# Precision_Arduino_Charlieplex_2_0.net
KiCad netlist of a schematic drawn in EAGLE
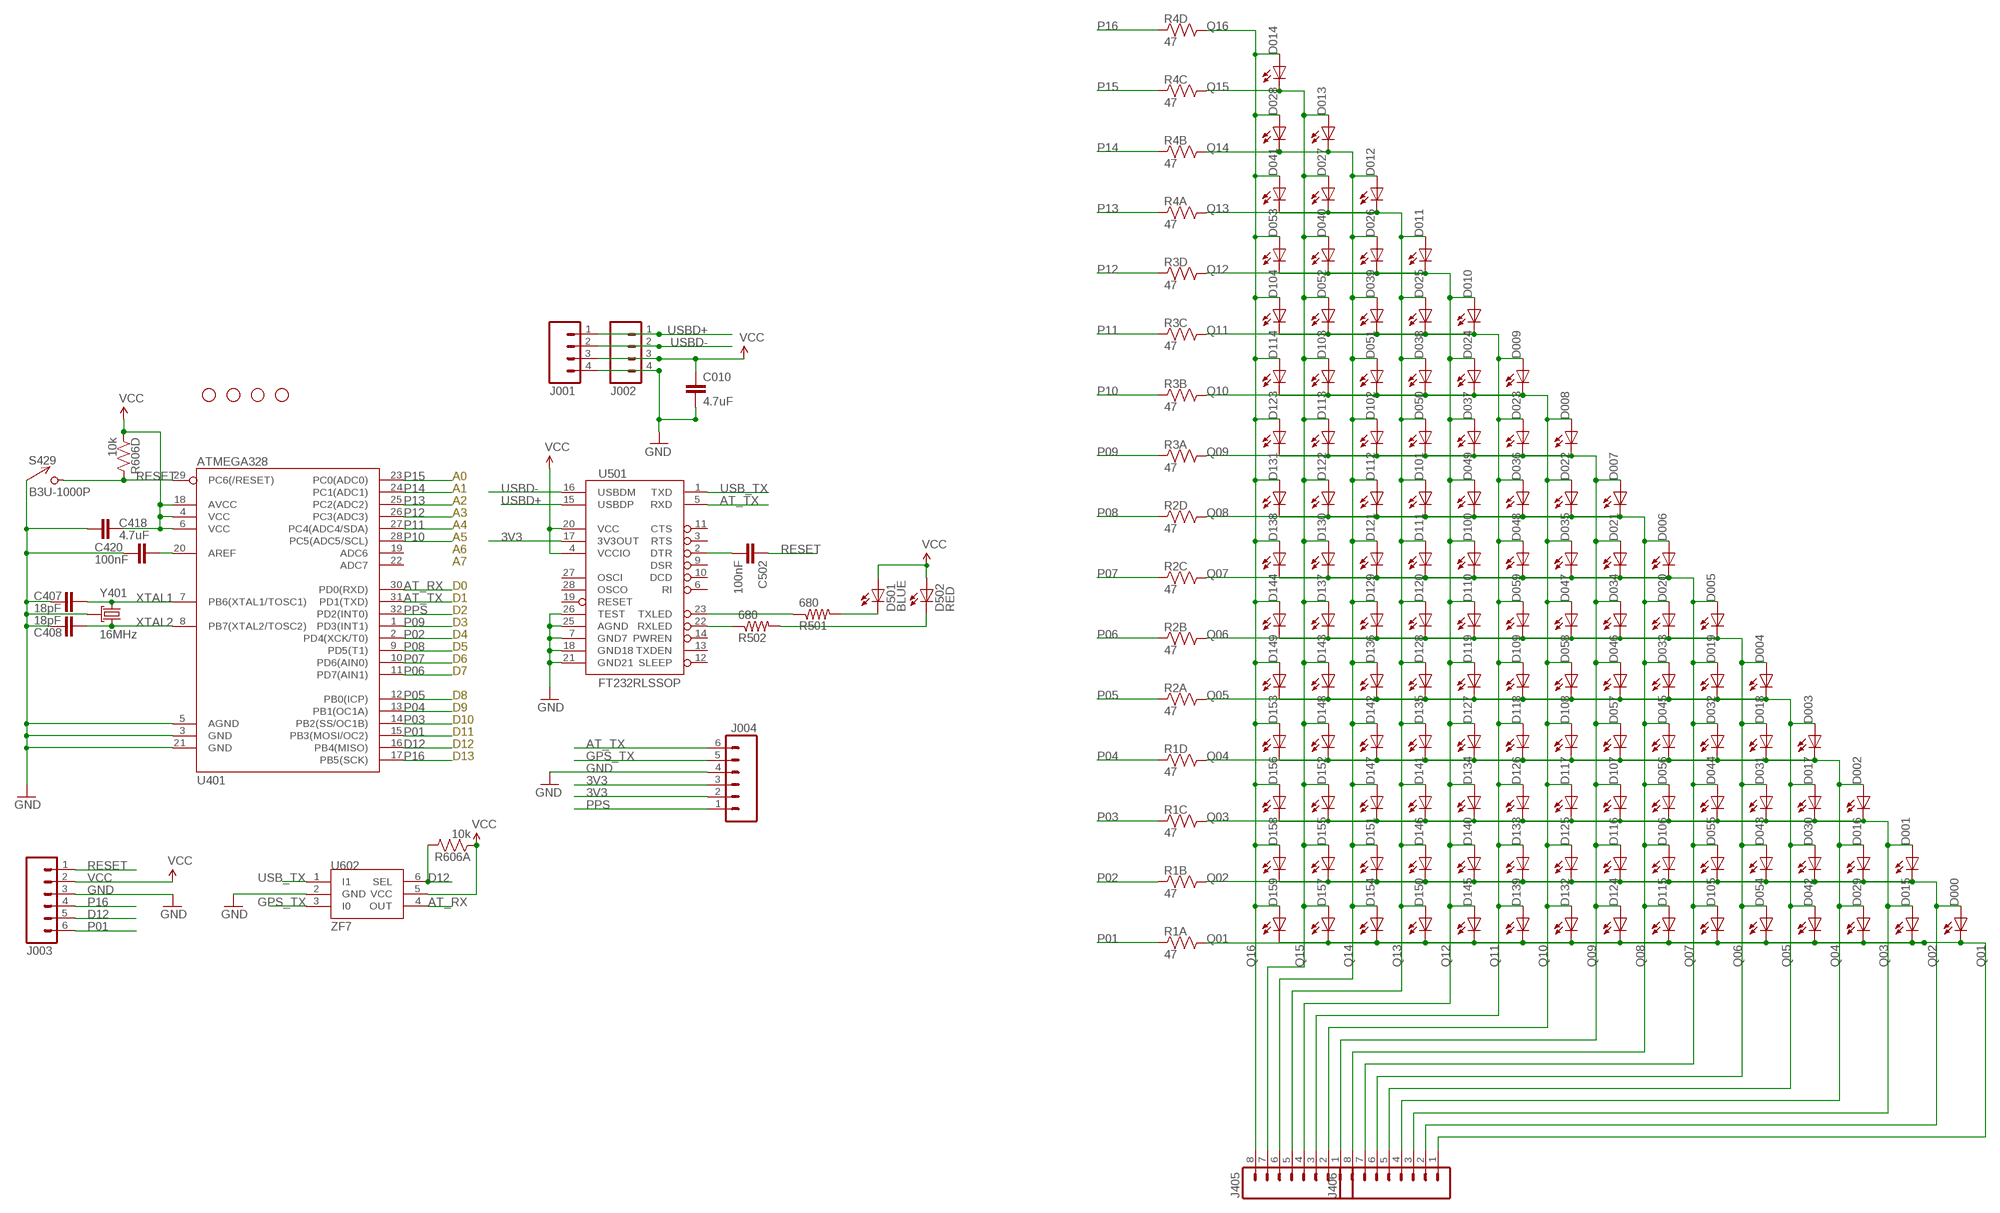
[diagram p0: schematic, sheet 1]

(export (version "E")
  (design (tool "Eeschema 10.0.6"))
  (components
    (comp (ref "C010")
      (value "4.7uF")
      (footprint "eagle-import:0603-CAP")
      (libsource (lib "eagle-import") (part "CAP0603-CAP"))
    )
    (comp (ref "C407")
      (value "18pF")
      (footprint "eagle-import:0603-CAP")
      (libsource (lib "eagle-import") (part "CAP0603-CAP"))
    )
    (comp (ref "C408")
      (value "18pF")
      (footprint "eagle-import:0603-CAP")
      (libsource (lib "eagle-import") (part "CAP0603-CAP"))
    )
    (comp (ref "C418")
      (value "4.7uF")
      (footprint "eagle-import:0603-CAP")
      (libsource (lib "eagle-import") (part "CAP0603-CAP"))
    )
    (comp (ref "C420")
      (value "100nF")
      (footprint "eagle-import:0603-CAP")
      (libsource (lib "eagle-import") (part "CAP0603-CAP"))
    )
    (comp (ref "C502")
      (value "100nF")
      (footprint "eagle-import:0603-CAP")
      (libsource (lib "eagle-import") (part "CAP0603-CAP"))
    )
    (comp (ref "D000")
      (value "HOUR")
      (footprint "eagle-import:LED-0603")
      (libsource (lib "eagle-import") (part "LED0603"))
    )
    (comp (ref "D001")
      (value "HOUR")
      (footprint "eagle-import:LED-0603")
      (libsource (lib "eagle-import") (part "LED0603"))
    )
    (comp (ref "D002")
      (value "HOUR")
      (footprint "eagle-import:LED-0603")
      (libsource (lib "eagle-import") (part "LED0603"))
    )
    (comp (ref "D003")
      (value "HOUR")
      (footprint "eagle-import:LED-0603")
      (libsource (lib "eagle-import") (part "LED0603"))
    )
    (comp (ref "D004")
      (value "HOUR")
      (footprint "eagle-import:LED-0603")
      (libsource (lib "eagle-import") (part "LED0603"))
    )
    (comp (ref "D005")
      (value "HOUR")
      (footprint "eagle-import:LED-0603")
      (libsource (lib "eagle-import") (part "LED0603"))
    )
    (comp (ref "D006")
      (value "HOUR")
      (footprint "eagle-import:LED-0603")
      (libsource (lib "eagle-import") (part "LED0603"))
    )
    (comp (ref "D007")
      (value "HOUR")
      (footprint "eagle-import:LED-0603")
      (libsource (lib "eagle-import") (part "LED0603"))
    )
    (comp (ref "D008")
      (value "HOUR")
      (footprint "eagle-import:LED-0603")
      (libsource (lib "eagle-import") (part "LED0603"))
    )
    (comp (ref "D009")
      (value "HOUR")
      (footprint "eagle-import:LED-0603")
      (libsource (lib "eagle-import") (part "LED0603"))
    )
    (comp (ref "D010")
      (value "HOUR")
      (footprint "eagle-import:LED-0603")
      (libsource (lib "eagle-import") (part "LED0603"))
    )
    (comp (ref "D011")
      (value "HOUR")
      (footprint "eagle-import:LED-0603")
      (libsource (lib "eagle-import") (part "LED0603"))
    )
    (comp (ref "D012")
      (value "HOUR")
      (footprint "eagle-import:LED-0603")
      (libsource (lib "eagle-import") (part "LED0603"))
    )
    (comp (ref "D013")
      (value "HOUR")
      (footprint "eagle-import:LED-0603")
      (libsource (lib "eagle-import") (part "LED0603"))
    )
    (comp (ref "D014")
      (value "HOUR")
      (footprint "eagle-import:LED-0603")
      (libsource (lib "eagle-import") (part "LED0603"))
    )
    (comp (ref "D015")
      (value "HOUR")
      (footprint "eagle-import:LED-0603")
      (libsource (lib "eagle-import") (part "LED0603"))
    )
    (comp (ref "D016")
      (value "HOUR")
      (footprint "eagle-import:LED-0603")
      (libsource (lib "eagle-import") (part "LED0603"))
    )
    (comp (ref "D017")
      (value "HOUR")
      (footprint "eagle-import:LED-0603")
      (libsource (lib "eagle-import") (part "LED0603"))
    )
    (comp (ref "D018")
      (value "HOUR")
      (footprint "eagle-import:LED-0603")
      (libsource (lib "eagle-import") (part "LED0603"))
    )
    (comp (ref "D019")
      (value "HOUR")
      (footprint "eagle-import:LED-0603")
      (libsource (lib "eagle-import") (part "LED0603"))
    )
    (comp (ref "D020")
      (value "HOUR")
      (footprint "eagle-import:LED-0603")
      (libsource (lib "eagle-import") (part "LED0603"))
    )
    (comp (ref "D021")
      (value "HOUR")
      (footprint "eagle-import:LED-0603")
      (libsource (lib "eagle-import") (part "LED0603"))
    )
    (comp (ref "D022")
      (value "HOUR")
      (footprint "eagle-import:LED-0603")
      (libsource (lib "eagle-import") (part "LED0603"))
    )
    (comp (ref "D023")
      (value "HOUR")
      (footprint "eagle-import:LED-0603")
      (libsource (lib "eagle-import") (part "LED0603"))
    )
    (comp (ref "D024")
      (value "HOUR")
      (footprint "eagle-import:LED-0603")
      (libsource (lib "eagle-import") (part "LED0603"))
    )
    (comp (ref "D025")
      (value "HOUR")
      (footprint "eagle-import:LED-0603")
      (libsource (lib "eagle-import") (part "LED0603"))
    )
    (comp (ref "D026")
      (value "HOUR")
      (footprint "eagle-import:LED-0603")
      (libsource (lib "eagle-import") (part "LED0603"))
    )
    (comp (ref "D027")
      (value "HOUR")
      (footprint "eagle-import:LED-0603")
      (libsource (lib "eagle-import") (part "LED0603"))
    )
    (comp (ref "D028")
      (value "HOUR")
      (footprint "eagle-import:LED-0603")
      (libsource (lib "eagle-import") (part "LED0603"))
    )
    (comp (ref "D029")
      (value "HOUR")
      (footprint "eagle-import:LED-0603")
      (libsource (lib "eagle-import") (part "LED0603"))
    )
    (comp (ref "D030")
      (value "HOUR")
      (footprint "eagle-import:LED-0603")
      (libsource (lib "eagle-import") (part "LED0603"))
    )
    (comp (ref "D031")
      (value "HOUR")
      (footprint "eagle-import:LED-0603")
      (libsource (lib "eagle-import") (part "LED0603"))
    )
    (comp (ref "D032")
      (value "HOUR")
      (footprint "eagle-import:LED-0603")
      (libsource (lib "eagle-import") (part "LED0603"))
    )
    (comp (ref "D033")
      (value "HOUR")
      (footprint "eagle-import:LED-0603")
      (libsource (lib "eagle-import") (part "LED0603"))
    )
    (comp (ref "D034")
      (value "HOUR")
      (footprint "eagle-import:LED-0603")
      (libsource (lib "eagle-import") (part "LED0603"))
    )
    (comp (ref "D035")
      (value "HOUR")
      (footprint "eagle-import:LED-0603")
      (libsource (lib "eagle-import") (part "LED0603"))
    )
    (comp (ref "D036")
      (value "HOUR")
      (footprint "eagle-import:LED-0603")
      (libsource (lib "eagle-import") (part "LED0603"))
    )
    (comp (ref "D037")
      (value "HOUR")
      (footprint "eagle-import:LED-0603")
      (libsource (lib "eagle-import") (part "LED0603"))
    )
    (comp (ref "D038")
      (value "HOUR")
      (footprint "eagle-import:LED-0603")
      (libsource (lib "eagle-import") (part "LED0603"))
    )
    (comp (ref "D039")
      (value "HOUR")
      (footprint "eagle-import:LED-0603")
      (libsource (lib "eagle-import") (part "LED0603"))
    )
    (comp (ref "D040")
      (value "HOUR")
      (footprint "eagle-import:LED-0603")
      (libsource (lib "eagle-import") (part "LED0603"))
    )
    (comp (ref "D041")
      (value "HOUR")
      (footprint "eagle-import:LED-0603")
      (libsource (lib "eagle-import") (part "LED0603"))
    )
    (comp (ref "D042")
      (value "HOUR")
      (footprint "eagle-import:LED-0603")
      (libsource (lib "eagle-import") (part "LED0603"))
    )
    (comp (ref "D043")
      (value "HOUR")
      (footprint "eagle-import:LED-0603")
      (libsource (lib "eagle-import") (part "LED0603"))
    )
    (comp (ref "D044")
      (value "HOUR")
      (footprint "eagle-import:LED-0603")
      (libsource (lib "eagle-import") (part "LED0603"))
    )
    (comp (ref "D045")
      (value "HOUR")
      (footprint "eagle-import:LED-0603")
      (libsource (lib "eagle-import") (part "LED0603"))
    )
    (comp (ref "D046")
      (value "HOUR")
      (footprint "eagle-import:LED-0603")
      (libsource (lib "eagle-import") (part "LED0603"))
    )
    (comp (ref "D047")
      (value "HOUR")
      (footprint "eagle-import:LED-0603")
      (libsource (lib "eagle-import") (part "LED0603"))
    )
    (comp (ref "D048")
      (value "HOUR")
      (footprint "eagle-import:LED-0603")
      (libsource (lib "eagle-import") (part "LED0603"))
    )
    (comp (ref "D049")
      (value "HOUR")
      (footprint "eagle-import:LED-0603")
      (libsource (lib "eagle-import") (part "LED0603"))
    )
    (comp (ref "D050")
      (value "HOUR")
      (footprint "eagle-import:LED-0603")
      (libsource (lib "eagle-import") (part "LED0603"))
    )
    (comp (ref "D051")
      (value "HOUR")
      (footprint "eagle-import:LED-0603")
      (libsource (lib "eagle-import") (part "LED0603"))
    )
    (comp (ref "D052")
      (value "HOUR")
      (footprint "eagle-import:LED-0603")
      (libsource (lib "eagle-import") (part "LED0603"))
    )
    (comp (ref "D053")
      (value "HOUR")
      (footprint "eagle-import:LED-0603")
      (libsource (lib "eagle-import") (part "LED0603"))
    )
    (comp (ref "D054")
      (value "HOUR")
      (footprint "eagle-import:LED-0603")
      (libsource (lib "eagle-import") (part "LED0603"))
    )
    (comp (ref "D055")
      (value "HOUR")
      (footprint "eagle-import:LED-0603")
      (libsource (lib "eagle-import") (part "LED0603"))
    )
    (comp (ref "D056")
      (value "HOUR")
      (footprint "eagle-import:LED-0603")
      (libsource (lib "eagle-import") (part "LED0603"))
    )
    (comp (ref "D057")
      (value "HOUR")
      (footprint "eagle-import:LED-0603")
      (libsource (lib "eagle-import") (part "LED0603"))
    )
    (comp (ref "D058")
      (value "HOUR")
      (footprint "eagle-import:LED-0603")
      (libsource (lib "eagle-import") (part "LED0603"))
    )
    (comp (ref "D059")
      (value "HOUR")
      (footprint "eagle-import:LED-0603")
      (libsource (lib "eagle-import") (part "LED0603"))
    )
    (comp (ref "D100")
      (value "HOUR")
      (footprint "eagle-import:LED-0603")
      (libsource (lib "eagle-import") (part "LED0603"))
    )
    (comp (ref "D101")
      (value "HOUR")
      (footprint "eagle-import:LED-0603")
      (libsource (lib "eagle-import") (part "LED0603"))
    )
    (comp (ref "D102")
      (value "HOUR")
      (footprint "eagle-import:LED-0603")
      (libsource (lib "eagle-import") (part "LED0603"))
    )
    (comp (ref "D103")
      (value "HOUR")
      (footprint "eagle-import:LED-0603")
      (libsource (lib "eagle-import") (part "LED0603"))
    )
    (comp (ref "D104")
      (value "HOUR")
      (footprint "eagle-import:LED-0603")
      (libsource (lib "eagle-import") (part "LED0603"))
    )
    (comp (ref "D105")
      (value "HOUR")
      (footprint "eagle-import:LED-0603")
      (libsource (lib "eagle-import") (part "LED0603"))
    )
    (comp (ref "D106")
      (value "HOUR")
      (footprint "eagle-import:LED-0603")
      (libsource (lib "eagle-import") (part "LED0603"))
    )
    (comp (ref "D107")
      (value "HOUR")
      (footprint "eagle-import:LED-0603")
      (libsource (lib "eagle-import") (part "LED0603"))
    )
    (comp (ref "D108")
      (value "HOUR")
      (footprint "eagle-import:LED-0603")
      (libsource (lib "eagle-import") (part "LED0603"))
    )
    (comp (ref "D109")
      (value "HOUR")
      (footprint "eagle-import:LED-0603")
      (libsource (lib "eagle-import") (part "LED0603"))
    )
    (comp (ref "D110")
      (value "HOUR")
      (footprint "eagle-import:LED-0603")
      (libsource (lib "eagle-import") (part "LED0603"))
    )
    (comp (ref "D111")
      (value "HOUR")
      (footprint "eagle-import:LED-0603")
      (libsource (lib "eagle-import") (part "LED0603"))
    )
    (comp (ref "D112")
      (value "HOUR")
      (footprint "eagle-import:LED-0603")
      (libsource (lib "eagle-import") (part "LED0603"))
    )
    (comp (ref "D113")
      (value "HOUR")
      (footprint "eagle-import:LED-0603")
      (libsource (lib "eagle-import") (part "LED0603"))
    )
    (comp (ref "D114")
      (value "HOUR")
      (footprint "eagle-import:LED-0603")
      (libsource (lib "eagle-import") (part "LED0603"))
    )
    (comp (ref "D115")
      (value "HOUR")
      (footprint "eagle-import:LED-0603")
      (libsource (lib "eagle-import") (part "LED0603"))
    )
    (comp (ref "D116")
      (value "HOUR")
      (footprint "eagle-import:LED-0603")
      (libsource (lib "eagle-import") (part "LED0603"))
    )
    (comp (ref "D117")
      (value "HOUR")
      (footprint "eagle-import:LED-0603")
      (libsource (lib "eagle-import") (part "LED0603"))
    )
    (comp (ref "D118")
      (value "HOUR")
      (footprint "eagle-import:LED-0603")
      (libsource (lib "eagle-import") (part "LED0603"))
    )
    (comp (ref "D119")
      (value "HOUR")
      (footprint "eagle-import:LED-0603")
      (libsource (lib "eagle-import") (part "LED0603"))
    )
    (comp (ref "D120")
      (value "HOUR")
      (footprint "eagle-import:LED-0603")
      (libsource (lib "eagle-import") (part "LED0603"))
    )
    (comp (ref "D121")
      (value "HOUR")
      (footprint "eagle-import:LED-0603")
      (libsource (lib "eagle-import") (part "LED0603"))
    )
    (comp (ref "D122")
      (value "HOUR")
      (footprint "eagle-import:LED-0603")
      (libsource (lib "eagle-import") (part "LED0603"))
    )
    (comp (ref "D123")
      (value "HOUR")
      (footprint "eagle-import:LED-0603")
      (libsource (lib "eagle-import") (part "LED0603"))
    )
    (comp (ref "D124")
      (value "HOUR")
      (footprint "eagle-import:LED-0603")
      (libsource (lib "eagle-import") (part "LED0603"))
    )
    (comp (ref "D125")
      (value "HOUR")
      (footprint "eagle-import:LED-0603")
      (libsource (lib "eagle-import") (part "LED0603"))
    )
    (comp (ref "D126")
      (value "HOUR")
      (footprint "eagle-import:LED-0603")
      (libsource (lib "eagle-import") (part "LED0603"))
    )
    (comp (ref "D127")
      (value "HOUR")
      (footprint "eagle-import:LED-0603")
      (libsource (lib "eagle-import") (part "LED0603"))
    )
    (comp (ref "D128")
      (value "HOUR")
      (footprint "eagle-import:LED-0603")
      (libsource (lib "eagle-import") (part "LED0603"))
    )
    (comp (ref "D129")
      (value "HOUR")
      (footprint "eagle-import:LED-0603")
      (libsource (lib "eagle-import") (part "LED0603"))
    )
    (comp (ref "D130")
      (value "HOUR")
      (footprint "eagle-import:LED-0603")
      (libsource (lib "eagle-import") (part "LED0603"))
    )
    (comp (ref "D131")
      (value "HOUR")
      (footprint "eagle-import:LED-0603")
      (libsource (lib "eagle-import") (part "LED0603"))
    )
    (comp (ref "D132")
      (value "HOUR")
      (footprint "eagle-import:LED-0603")
      (libsource (lib "eagle-import") (part "LED0603"))
    )
    (comp (ref "D133")
      (value "HOUR")
      (footprint "eagle-import:LED-0603")
      (libsource (lib "eagle-import") (part "LED0603"))
    )
    (comp (ref "D134")
      (value "HOUR")
      (footprint "eagle-import:LED-0603")
      (libsource (lib "eagle-import") (part "LED0603"))
    )
    (comp (ref "D135")
      (value "HOUR")
      (footprint "eagle-import:LED-0603")
      (libsource (lib "eagle-import") (part "LED0603"))
    )
    (comp (ref "D136")
      (value "HOUR")
      (footprint "eagle-import:LED-0603")
      (libsource (lib "eagle-import") (part "LED0603"))
    )
    (comp (ref "D137")
      (value "HOUR")
      (footprint "eagle-import:LED-0603")
      (libsource (lib "eagle-import") (part "LED0603"))
    )
    (comp (ref "D138")
      (value "HOUR")
      (footprint "eagle-import:LED-0603")
      (libsource (lib "eagle-import") (part "LED0603"))
    )
    (comp (ref "D139")
      (value "HOUR")
      (footprint "eagle-import:LED-0603")
      (libsource (lib "eagle-import") (part "LED0603"))
    )
    (comp (ref "D140")
      (value "HOUR")
      (footprint "eagle-import:LED-0603")
      (libsource (lib "eagle-import") (part "LED0603"))
    )
    (comp (ref "D141")
      (value "HOUR")
      (footprint "eagle-import:LED-0603")
      (libsource (lib "eagle-import") (part "LED0603"))
    )
    (comp (ref "D142")
      (value "HOUR")
      (footprint "eagle-import:LED-0603")
      (libsource (lib "eagle-import") (part "LED0603"))
    )
    (comp (ref "D143")
      (value "HOUR")
      (footprint "eagle-import:LED-0603")
      (libsource (lib "eagle-import") (part "LED0603"))
    )
    (comp (ref "D144")
      (value "HOUR")
      (footprint "eagle-import:LED-0603")
      (libsource (lib "eagle-import") (part "LED0603"))
    )
    (comp (ref "D145")
      (value "HOUR")
      (footprint "eagle-import:LED-0603")
      (libsource (lib "eagle-import") (part "LED0603"))
    )
    (comp (ref "D146")
      (value "HOUR")
      (footprint "eagle-import:LED-0603")
      (libsource (lib "eagle-import") (part "LED0603"))
    )
    (comp (ref "D147")
      (value "HOUR")
      (footprint "eagle-import:LED-0603")
      (libsource (lib "eagle-import") (part "LED0603"))
    )
    (comp (ref "D148")
      (value "HOUR")
      (footprint "eagle-import:LED-0603")
      (libsource (lib "eagle-import") (part "LED0603"))
    )
    (comp (ref "D149")
      (value "HOUR")
      (footprint "eagle-import:LED-0603")
      (libsource (lib "eagle-import") (part "LED0603"))
    )
    (comp (ref "D150")
      (value "HOUR")
      (footprint "eagle-import:LED-0603")
      (libsource (lib "eagle-import") (part "LED0603"))
    )
    (comp (ref "D151")
      (value "HOUR")
      (footprint "eagle-import:LED-0603")
      (libsource (lib "eagle-import") (part "LED0603"))
    )
    (comp (ref "D152")
      (value "HOUR")
      (footprint "eagle-import:LED-0603")
      (libsource (lib "eagle-import") (part "LED0603"))
    )
    (comp (ref "D153")
      (value "HOUR")
      (footprint "eagle-import:LED-0603")
      (libsource (lib "eagle-import") (part "LED0603"))
    )
    (comp (ref "D154")
      (value "HOUR")
      (footprint "eagle-import:LED-0603")
      (libsource (lib "eagle-import") (part "LED0603"))
    )
    (comp (ref "D155")
      (value "HOUR")
      (footprint "eagle-import:LED-0603")
      (libsource (lib "eagle-import") (part "LED0603"))
    )
    (comp (ref "D156")
      (value "HOUR")
      (footprint "eagle-import:LED-0603")
      (libsource (lib "eagle-import") (part "LED0603"))
    )
    (comp (ref "D157")
      (value "HOUR")
      (footprint "eagle-import:LED-0603")
      (libsource (lib "eagle-import") (part "LED0603"))
    )
    (comp (ref "D158")
      (value "HOUR")
      (footprint "eagle-import:LED-0603")
      (libsource (lib "eagle-import") (part "LED0603"))
    )
    (comp (ref "D159")
      (value "HOUR")
      (footprint "eagle-import:LED-0603")
      (libsource (lib "eagle-import") (part "LED0603"))
    )
    (comp (ref "D501")
      (value "BLUE")
      (footprint "eagle-import:LED-0603")
      (libsource (lib "eagle-import") (part "LED0603"))
    )
    (comp (ref "D502")
      (value "RED")
      (footprint "eagle-import:LED-0603")
      (libsource (lib "eagle-import") (part "LED0603"))
    )
    (comp (ref "J001")
      (value "M04PTH")
      (footprint "eagle-import:1X04")
      (libsource (lib "eagle-import") (part "M04PTH"))
    )
    (comp (ref "J002")
      (value "M04PTH")
      (footprint "eagle-import:1X04")
      (libsource (lib "eagle-import") (part "M04PTH"))
    )
    (comp (ref "J003")
      (value "M06SIP")
      (footprint "eagle-import:1X06")
      (libsource (lib "eagle-import") (part "M06SIP"))
    )
    (comp (ref "J004")
      (value "M06SIP")
      (footprint "eagle-import:1X06")
      (libsource (lib "eagle-import") (part "M06SIP"))
    )
    (comp (ref "J405")
      (value "M081X08")
      (footprint "eagle-import:1X08")
      (libsource (lib "eagle-import") (part "M081X08"))
    )
    (comp (ref "J406")
      (value "M081X08")
      (footprint "eagle-import:1X08")
      (libsource (lib "eagle-import") (part "M081X08"))
    )
    (comp (ref "JP1")
      (value "STAND-OFF")
      (footprint "eagle-import:STAND-OFF")
      (libsource (lib "eagle-import") (part "STAND-OFF"))
    )
    (comp (ref "JP2")
      (value "STAND-OFF")
      (footprint "eagle-import:STAND-OFF")
      (libsource (lib "eagle-import") (part "STAND-OFF"))
    )
    (comp (ref "JP3")
      (value "STAND-OFF")
      (footprint "eagle-import:STAND-OFF")
      (libsource (lib "eagle-import") (part "STAND-OFF"))
    )
    (comp (ref "JP4")
      (value "STAND-OFF")
      (footprint "eagle-import:STAND-OFF")
      (libsource (lib "eagle-import") (part "STAND-OFF"))
    )
    (comp (ref "R1")
      (value "47")
      (footprint "eagle-import:CRA04")
      (libsource (lib "eagle-import") (part "RP404"))
    )
    (comp (ref "R2")
      (value "47")
      (footprint "eagle-import:CRA04")
      (libsource (lib "eagle-import") (part "RP404"))
    )
    (comp (ref "R3")
      (value "47")
      (footprint "eagle-import:CRA04")
      (libsource (lib "eagle-import") (part "RP404"))
    )
    (comp (ref "R4")
      (value "47")
      (footprint "eagle-import:CRA04")
      (libsource (lib "eagle-import") (part "RP404"))
    )
    (comp (ref "R501")
      (value "680")
      (footprint "eagle-import:0603-RES")
      (libsource (lib "eagle-import") (part "RESISTOR0603-RES"))
    )
    (comp (ref "R502")
      (value "680")
      (footprint "eagle-import:0603-RES")
      (libsource (lib "eagle-import") (part "RESISTOR0603-RES"))
    )
    (comp (ref "R606")
      (value "10k")
      (footprint "eagle-import:CRA04")
      (libsource (lib "eagle-import") (part "RP404"))
    )
    (comp (ref "S429")
      (value "B3U-1000P")
      (footprint "eagle-import:B3U-1000P")
      (libsource (lib "eagle-import") (part "B3U-1000P"))
    )
    (comp (ref "U401")
      (value "ATMEGA328")
      (footprint "eagle-import:TQFP32-08")
      (libsource (lib "eagle-import") (part "ATMEGA168"))
    )
    (comp (ref "U501")
      (value "FT232RLSSOP")
      (footprint "eagle-import:SSOP28DB")
      (libsource (lib "eagle-import") (part "FT232RLSSOP"))
    )
    (comp (ref "U602")
      (value "ZF7")
      (footprint "eagle-import:SC-70-6")
      (libsource (lib "eagle-import") (part "NC7SZ157"))
    )
    (comp (ref "Y401")
      (value "16MHz")
      (footprint "eagle-import:CRYSTAL_SMD")
      (libsource (lib "eagle-import") (part "TSX-3225"))
    )
  )
  (nets
    (net (code "1") (name "/3V3") (class "Default")
      (node (ref "J004") (pin "2") (pinfunction "2_2") (pintype "passive"))
      (node (ref "J004") (pin "3") (pinfunction "3_3") (pintype "passive"))
      (node (ref "U501") (pin "17") (pinfunction "3V3OUT_17") (pintype "output"))
    )
    (net (code "2") (name "/AT_RX") (class "Default")
      (node (ref "U401") (pin "30") (pinfunction "PD0(RXD)_30") (pintype "bidirectional"))
      (node (ref "U602") (pin "4") (pinfunction "OUT_4") (pintype "bidirectional"))
    )
    (net (code "3") (name "/AT_TX") (class "Default")
      (node (ref "J004") (pin "6") (pinfunction "6_6") (pintype "passive"))
      (node (ref "U401") (pin "31") (pinfunction "PD1(TXD)_31") (pintype "bidirectional"))
      (node (ref "U501") (pin "5") (pinfunction "RXD_5") (pintype "input"))
    )
    (net (code "4") (name "/D12") (class "Default")
      (node (ref "J003") (pin "5") (pinfunction "5_5") (pintype "passive"))
      (node (ref "R606") (pin "8") (pinfunction "2_8") (pintype "passive"))
      (node (ref "U401") (pin "16") (pinfunction "PB4(MISO)_16") (pintype "bidirectional"))
      (node (ref "U602") (pin "6") (pinfunction "SEL_6") (pintype "bidirectional"))
    )
    (net (code "5") (name "/GPS_TX") (class "Default")
      (node (ref "J004") (pin "5") (pinfunction "5_5") (pintype "passive"))
      (node (ref "U602") (pin "3") (pinfunction "I0_3") (pintype "bidirectional"))
    )
    (net (code "6") (name "/P01") (class "Default")
      (node (ref "J003") (pin "6") (pinfunction "6_6") (pintype "passive"))
      (node (ref "R1") (pin "1") (pinfunction "1_1") (pintype "passive"))
      (node (ref "U401") (pin "15") (pinfunction "PB3(MOSI/OC2)_15") (pintype "bidirectional"))
    )
    (net (code "7") (name "/P02") (class "Default")
      (node (ref "R1") (pin "2") (pinfunction "1_2") (pintype "passive"))
      (node (ref "U401") (pin "2") (pinfunction "PD4(XCK/T0)_2") (pintype "bidirectional"))
    )
    (net (code "8") (name "/P03") (class "Default")
      (node (ref "R1") (pin "3") (pinfunction "1_3") (pintype "passive"))
      (node (ref "U401") (pin "14") (pinfunction "PB2(SS/OC1B)_14") (pintype "bidirectional"))
    )
    (net (code "9") (name "/P04") (class "Default")
      (node (ref "R1") (pin "4") (pinfunction "1_4") (pintype "passive"))
      (node (ref "U401") (pin "13") (pinfunction "PB1(OC1A)_13") (pintype "bidirectional"))
    )
    (net (code "10") (name "/P05") (class "Default")
      (node (ref "R2") (pin "1") (pinfunction "1_1") (pintype "passive"))
      (node (ref "U401") (pin "12") (pinfunction "PB0(ICP)_12") (pintype "bidirectional"))
    )
    (net (code "11") (name "/P06") (class "Default")
      (node (ref "R2") (pin "2") (pinfunction "1_2") (pintype "passive"))
      (node (ref "U401") (pin "11") (pinfunction "PD7(AIN1)_11") (pintype "bidirectional"))
    )
    (net (code "12") (name "/P07") (class "Default")
      (node (ref "R2") (pin "3") (pinfunction "1_3") (pintype "passive"))
      (node (ref "U401") (pin "10") (pinfunction "PD6(AIN0)_10") (pintype "bidirectional"))
    )
    (net (code "13") (name "/P08") (class "Default")
      (node (ref "R2") (pin "4") (pinfunction "1_4") (pintype "passive"))
      (node (ref "U401") (pin "9") (pinfunction "PD5(T1)_9") (pintype "bidirectional"))
    )
    (net (code "14") (name "/P09") (class "Default")
      (node (ref "R3") (pin "1") (pinfunction "1_1") (pintype "passive"))
      (node (ref "U401") (pin "1") (pinfunction "PD3(INT1)_1") (pintype "bidirectional"))
    )
    (net (code "15") (name "/P10") (class "Default")
      (node (ref "R3") (pin "2") (pinfunction "1_2") (pintype "passive"))
      (node (ref "U401") (pin "28") (pinfunction "PC5(ADC5/SCL)_28") (pintype "bidirectional"))
    )
    (net (code "16") (name "/P11") (class "Default")
      (node (ref "R3") (pin "3") (pinfunction "1_3") (pintype "passive"))
      (node (ref "U401") (pin "27") (pinfunction "PC4(ADC4/SDA)_27") (pintype "bidirectional"))
    )
    (net (code "17") (name "/P12") (class "Default")
      (node (ref "R3") (pin "4") (pinfunction "1_4") (pintype "passive"))
      (node (ref "U401") (pin "26") (pinfunction "PC3(ADC3)_26") (pintype "bidirectional"))
    )
    (net (code "18") (name "/P13") (class "Default")
      (node (ref "R4") (pin "1") (pinfunction "1_1") (pintype "passive"))
      (node (ref "U401") (pin "25") (pinfunction "PC2(ADC2)_25") (pintype "bidirectional"))
    )
    (net (code "19") (name "/P14") (class "Default")
      (node (ref "R4") (pin "2") (pinfunction "1_2") (pintype "passive"))
      (node (ref "U401") (pin "24") (pinfunction "PC1(ADC1)_24") (pintype "bidirectional"))
    )
    (net (code "20") (name "/P15") (class "Default")
      (node (ref "R4") (pin "3") (pinfunction "1_3") (pintype "passive"))
      (node (ref "U401") (pin "23") (pinfunction "PC0(ADC0)_23") (pintype "bidirectional"))
    )
    (net (code "21") (name "/P16") (class "Default")
      (node (ref "J003") (pin "4") (pinfunction "4_4") (pintype "passive"))
      (node (ref "R4") (pin "4") (pinfunction "1_4") (pintype "passive"))
      (node (ref "U401") (pin "17") (pinfunction "PB5(SCK)_17") (pintype "bidirectional"))
    )
    (net (code "22") (name "/PPS") (class "Default")
      (node (ref "J004") (pin "1") (pinfunction "1_1") (pintype "passive"))
      (node (ref "U401") (pin "32") (pinfunction "PD2(INT0)_32") (pintype "bidirectional"))
    )
    (net (code "23") (name "/Q01") (class "Default")
      (node (ref "D000") (pin "C") (pinfunction "C_C") (pintype "passive"))
      (node (ref "D015") (pin "C") (pinfunction "C_C") (pintype "passive"))
      (node (ref "D029") (pin "C") (pinfunction "C_C") (pintype "passive"))
      (node (ref "D042") (pin "C") (pinfunction "C_C") (pintype "passive"))
      (node (ref "D054") (pin "C") (pinfunction "C_C") (pintype "passive"))
      (node (ref "D105") (pin "C") (pinfunction "C_C") (pintype "passive"))
      (node (ref "D115") (pin "C") (pinfunction "C_C") (pintype "passive"))
      (node (ref "D124") (pin "C") (pinfunction "C_C") (pintype "passive"))
      (node (ref "D132") (pin "C") (pinfunction "C_C") (pintype "passive"))
      (node (ref "D139") (pin "C") (pinfunction "C_C") (pintype "passive"))
      (node (ref "D145") (pin "C") (pinfunction "C_C") (pintype "passive"))
      (node (ref "D150") (pin "C") (pinfunction "C_C") (pintype "passive"))
      (node (ref "D154") (pin "C") (pinfunction "C_C") (pintype "passive"))
      (node (ref "D157") (pin "C") (pinfunction "C_C") (pintype "passive"))
      (node (ref "D159") (pin "C") (pinfunction "C_C") (pintype "passive"))
      (node (ref "J406") (pin "1") (pinfunction "1_1") (pintype "passive"))
      (node (ref "R1") (pin "8") (pinfunction "2_8") (pintype "passive"))
    )
    (net (code "24") (name "/Q02") (class "Default")
      (node (ref "D000") (pin "A") (pinfunction "A_A") (pintype "passive"))
      (node (ref "D001") (pin "C") (pinfunction "C_C") (pintype "passive"))
      (node (ref "D016") (pin "C") (pinfunction "C_C") (pintype "passive"))
      (node (ref "D030") (pin "C") (pinfunction "C_C") (pintype "passive"))
      (node (ref "D043") (pin "C") (pinfunction "C_C") (pintype "passive"))
      (node (ref "D055") (pin "C") (pinfunction "C_C") (pintype "passive"))
      (node (ref "D106") (pin "C") (pinfunction "C_C") (pintype "passive"))
      (node (ref "D116") (pin "C") (pinfunction "C_C") (pintype "passive"))
      (node (ref "D125") (pin "C") (pinfunction "C_C") (pintype "passive"))
      (node (ref "D133") (pin "C") (pinfunction "C_C") (pintype "passive"))
      (node (ref "D140") (pin "C") (pinfunction "C_C") (pintype "passive"))
      (node (ref "D146") (pin "C") (pinfunction "C_C") (pintype "passive"))
      (node (ref "D151") (pin "C") (pinfunction "C_C") (pintype "passive"))
      (node (ref "D155") (pin "C") (pinfunction "C_C") (pintype "passive"))
      (node (ref "D158") (pin "C") (pinfunction "C_C") (pintype "passive"))
      (node (ref "J406") (pin "2") (pinfunction "2_2") (pintype "passive"))
      (node (ref "R1") (pin "7") (pinfunction "2_7") (pintype "passive"))
    )
    (net (code "25") (name "/Q03") (class "Default")
      (node (ref "D001") (pin "A") (pinfunction "A_A") (pintype "passive"))
      (node (ref "D002") (pin "C") (pinfunction "C_C") (pintype "passive"))
      (node (ref "D015") (pin "A") (pinfunction "A_A") (pintype "passive"))
      (node (ref "D017") (pin "C") (pinfunction "C_C") (pintype "passive"))
      (node (ref "D031") (pin "C") (pinfunction "C_C") (pintype "passive"))
      (node (ref "D044") (pin "C") (pinfunction "C_C") (pintype "passive"))
      (node (ref "D056") (pin "C") (pinfunction "C_C") (pintype "passive"))
      (node (ref "D107") (pin "C") (pinfunction "C_C") (pintype "passive"))
      (node (ref "D117") (pin "C") (pinfunction "C_C") (pintype "passive"))
      (node (ref "D126") (pin "C") (pinfunction "C_C") (pintype "passive"))
      (node (ref "D134") (pin "C") (pinfunction "C_C") (pintype "passive"))
      (node (ref "D141") (pin "C") (pinfunction "C_C") (pintype "passive"))
      (node (ref "D147") (pin "C") (pinfunction "C_C") (pintype "passive"))
      (node (ref "D152") (pin "C") (pinfunction "C_C") (pintype "passive"))
      (node (ref "D156") (pin "C") (pinfunction "C_C") (pintype "passive"))
      (node (ref "J406") (pin "3") (pinfunction "3_3") (pintype "passive"))
      (node (ref "R1") (pin "6") (pinfunction "2_6") (pintype "passive"))
    )
    (net (code "26") (name "/Q04") (class "Default")
      (node (ref "D002") (pin "A") (pinfunction "A_A") (pintype "passive"))
      (node (ref "D003") (pin "C") (pinfunction "C_C") (pintype "passive"))
      (node (ref "D016") (pin "A") (pinfunction "A_A") (pintype "passive"))
      (node (ref "D018") (pin "C") (pinfunction "C_C") (pintype "passive"))
      (node (ref "D029") (pin "A") (pinfunction "A_A") (pintype "passive"))
      (node (ref "D032") (pin "C") (pinfunction "C_C") (pintype "passive"))
      (node (ref "D045") (pin "C") (pinfunction "C_C") (pintype "passive"))
      (node (ref "D057") (pin "C") (pinfunction "C_C") (pintype "passive"))
      (node (ref "D108") (pin "C") (pinfunction "C_C") (pintype "passive"))
      (node (ref "D118") (pin "C") (pinfunction "C_C") (pintype "passive"))
      (node (ref "D127") (pin "C") (pinfunction "C_C") (pintype "passive"))
      (node (ref "D135") (pin "C") (pinfunction "C_C") (pintype "passive"))
      (node (ref "D142") (pin "C") (pinfunction "C_C") (pintype "passive"))
      (node (ref "D148") (pin "C") (pinfunction "C_C") (pintype "passive"))
      (node (ref "D153") (pin "C") (pinfunction "C_C") (pintype "passive"))
      (node (ref "J406") (pin "4") (pinfunction "4_4") (pintype "passive"))
      (node (ref "R1") (pin "5") (pinfunction "2_5") (pintype "passive"))
    )
    (net (code "27") (name "/Q05") (class "Default")
      (node (ref "D003") (pin "A") (pinfunction "A_A") (pintype "passive"))
      (node (ref "D004") (pin "C") (pinfunction "C_C") (pintype "passive"))
      (node (ref "D017") (pin "A") (pinfunction "A_A") (pintype "passive"))
      (node (ref "D019") (pin "C") (pinfunction "C_C") (pintype "passive"))
      (node (ref "D030") (pin "A") (pinfunction "A_A") (pintype "passive"))
      (node (ref "D033") (pin "C") (pinfunction "C_C") (pintype "passive"))
      (node (ref "D042") (pin "A") (pinfunction "A_A") (pintype "passive"))
      (node (ref "D046") (pin "C") (pinfunction "C_C") (pintype "passive"))
      (node (ref "D058") (pin "C") (pinfunction "C_C") (pintype "passive"))
      (node (ref "D109") (pin "C") (pinfunction "C_C") (pintype "passive"))
      (node (ref "D119") (pin "C") (pinfunction "C_C") (pintype "passive"))
      (node (ref "D128") (pin "C") (pinfunction "C_C") (pintype "passive"))
      (node (ref "D136") (pin "C") (pinfunction "C_C") (pintype "passive"))
      (node (ref "D143") (pin "C") (pinfunction "C_C") (pintype "passive"))
      (node (ref "D149") (pin "C") (pinfunction "C_C") (pintype "passive"))
      (node (ref "J406") (pin "5") (pinfunction "5_5") (pintype "passive"))
      (node (ref "R2") (pin "8") (pinfunction "2_8") (pintype "passive"))
    )
    (net (code "28") (name "/Q06") (class "Default")
      (node (ref "D004") (pin "A") (pinfunction "A_A") (pintype "passive"))
      (node (ref "D005") (pin "C") (pinfunction "C_C") (pintype "passive"))
      (node (ref "D018") (pin "A") (pinfunction "A_A") (pintype "passive"))
      (node (ref "D020") (pin "C") (pinfunction "C_C") (pintype "passive"))
      (node (ref "D031") (pin "A") (pinfunction "A_A") (pintype "passive"))
      (node (ref "D034") (pin "C") (pinfunction "C_C") (pintype "passive"))
      (node (ref "D043") (pin "A") (pinfunction "A_A") (pintype "passive"))
      (node (ref "D047") (pin "C") (pinfunction "C_C") (pintype "passive"))
      (node (ref "D054") (pin "A") (pinfunction "A_A") (pintype "passive"))
      (node (ref "D059") (pin "C") (pinfunction "C_C") (pintype "passive"))
      (node (ref "D110") (pin "C") (pinfunction "C_C") (pintype "passive"))
      (node (ref "D120") (pin "C") (pinfunction "C_C") (pintype "passive"))
      (node (ref "D129") (pin "C") (pinfunction "C_C") (pintype "passive"))
      (node (ref "D137") (pin "C") (pinfunction "C_C") (pintype "passive"))
      (node (ref "D144") (pin "C") (pinfunction "C_C") (pintype "passive"))
      (node (ref "J406") (pin "6") (pinfunction "6_6") (pintype "passive"))
      (node (ref "R2") (pin "7") (pinfunction "2_7") (pintype "passive"))
    )
    (net (code "29") (name "/Q07") (class "Default")
      (node (ref "D005") (pin "A") (pinfunction "A_A") (pintype "passive"))
      (node (ref "D006") (pin "C") (pinfunction "C_C") (pintype "passive"))
      (node (ref "D019") (pin "A") (pinfunction "A_A") (pintype "passive"))
      (node (ref "D021") (pin "C") (pinfunction "C_C") (pintype "passive"))
      (node (ref "D032") (pin "A") (pinfunction "A_A") (pintype "passive"))
      (node (ref "D035") (pin "C") (pinfunction "C_C") (pintype "passive"))
      (node (ref "D044") (pin "A") (pinfunction "A_A") (pintype "passive"))
      (node (ref "D048") (pin "C") (pinfunction "C_C") (pintype "passive"))
      (node (ref "D055") (pin "A") (pinfunction "A_A") (pintype "passive"))
      (node (ref "D100") (pin "C") (pinfunction "C_C") (pintype "passive"))
      (node (ref "D105") (pin "A") (pinfunction "A_A") (pintype "passive"))
      (node (ref "D111") (pin "C") (pinfunction "C_C") (pintype "passive"))
      (node (ref "D121") (pin "C") (pinfunction "C_C") (pintype "passive"))
      (node (ref "D130") (pin "C") (pinfunction "C_C") (pintype "passive"))
      (node (ref "D138") (pin "C") (pinfunction "C_C") (pintype "passive"))
      (node (ref "J406") (pin "7") (pinfunction "7_7") (pintype "passive"))
      (node (ref "R2") (pin "6") (pinfunction "2_6") (pintype "passive"))
    )
    (net (code "30") (name "/Q08") (class "Default")
      (node (ref "D006") (pin "A") (pinfunction "A_A") (pintype "passive"))
      (node (ref "D007") (pin "C") (pinfunction "C_C") (pintype "passive"))
      (node (ref "D020") (pin "A") (pinfunction "A_A") (pintype "passive"))
      (node (ref "D022") (pin "C") (pinfunction "C_C") (pintype "passive"))
      (node (ref "D033") (pin "A") (pinfunction "A_A") (pintype "passive"))
      (node (ref "D036") (pin "C") (pinfunction "C_C") (pintype "passive"))
      (node (ref "D045") (pin "A") (pinfunction "A_A") (pintype "passive"))
      (node (ref "D049") (pin "C") (pinfunction "C_C") (pintype "passive"))
      (node (ref "D056") (pin "A") (pinfunction "A_A") (pintype "passive"))
      (node (ref "D101") (pin "C") (pinfunction "C_C") (pintype "passive"))
      (node (ref "D106") (pin "A") (pinfunction "A_A") (pintype "passive"))
      (node (ref "D112") (pin "C") (pinfunction "C_C") (pintype "passive"))
      (node (ref "D115") (pin "A") (pinfunction "A_A") (pintype "passive"))
      (node (ref "D122") (pin "C") (pinfunction "C_C") (pintype "passive"))
      (node (ref "D131") (pin "C") (pinfunction "C_C") (pintype "passive"))
      (node (ref "J406") (pin "8") (pinfunction "8_8") (pintype "passive"))
      (node (ref "R2") (pin "5") (pinfunction "2_5") (pintype "passive"))
    )
    (net (code "31") (name "/Q09") (class "Default")
      (node (ref "D007") (pin "A") (pinfunction "A_A") (pintype "passive"))
      (node (ref "D008") (pin "C") (pinfunction "C_C") (pintype "passive"))
      (node (ref "D021") (pin "A") (pinfunction "A_A") (pintype "passive"))
      (node (ref "D023") (pin "C") (pinfunction "C_C") (pintype "passive"))
      (node (ref "D034") (pin "A") (pinfunction "A_A") (pintype "passive"))
      (node (ref "D037") (pin "C") (pinfunction "C_C") (pintype "passive"))
      (node (ref "D046") (pin "A") (pinfunction "A_A") (pintype "passive"))
      (node (ref "D050") (pin "C") (pinfunction "C_C") (pintype "passive"))
      (node (ref "D057") (pin "A") (pinfunction "A_A") (pintype "passive"))
      (node (ref "D102") (pin "C") (pinfunction "C_C") (pintype "passive"))
      (node (ref "D107") (pin "A") (pinfunction "A_A") (pintype "passive"))
      (node (ref "D113") (pin "C") (pinfunction "C_C") (pintype "passive"))
      (node (ref "D116") (pin "A") (pinfunction "A_A") (pintype "passive"))
      (node (ref "D123") (pin "C") (pinfunction "C_C") (pintype "passive"))
      (node (ref "D124") (pin "A") (pinfunction "A_A") (pintype "passive"))
      (node (ref "J405") (pin "1") (pinfunction "1_1") (pintype "passive"))
      (node (ref "R3") (pin "8") (pinfunction "2_8") (pintype "passive"))
    )
    (net (code "32") (name "/Q10") (class "Default")
      (node (ref "D008") (pin "A") (pinfunction "A_A") (pintype "passive"))
      (node (ref "D009") (pin "C") (pinfunction "C_C") (pintype "passive"))
      (node (ref "D022") (pin "A") (pinfunction "A_A") (pintype "passive"))
      (node (ref "D024") (pin "C") (pinfunction "C_C") (pintype "passive"))
      (node (ref "D035") (pin "A") (pinfunction "A_A") (pintype "passive"))
      (node (ref "D038") (pin "C") (pinfunction "C_C") (pintype "passive"))
      (node (ref "D047") (pin "A") (pinfunction "A_A") (pintype "passive"))
      (node (ref "D051") (pin "C") (pinfunction "C_C") (pintype "passive"))
      (node (ref "D058") (pin "A") (pinfunction "A_A") (pintype "passive"))
      (node (ref "D103") (pin "C") (pinfunction "C_C") (pintype "passive"))
      (node (ref "D108") (pin "A") (pinfunction "A_A") (pintype "passive"))
      (node (ref "D114") (pin "C") (pinfunction "C_C") (pintype "passive"))
      (node (ref "D117") (pin "A") (pinfunction "A_A") (pintype "passive"))
      (node (ref "D125") (pin "A") (pinfunction "A_A") (pintype "passive"))
      (node (ref "D132") (pin "A") (pinfunction "A_A") (pintype "passive"))
      (node (ref "J405") (pin "2") (pinfunction "2_2") (pintype "passive"))
      (node (ref "R3") (pin "7") (pinfunction "2_7") (pintype "passive"))
    )
    (net (code "33") (name "/Q11") (class "Default")
      (node (ref "D009") (pin "A") (pinfunction "A_A") (pintype "passive"))
      (node (ref "D010") (pin "C") (pinfunction "C_C") (pintype "passive"))
      (node (ref "D023") (pin "A") (pinfunction "A_A") (pintype "passive"))
      (node (ref "D025") (pin "C") (pinfunction "C_C") (pintype "passive"))
      (node (ref "D036") (pin "A") (pinfunction "A_A") (pintype "passive"))
      (node (ref "D039") (pin "C") (pinfunction "C_C") (pintype "passive"))
      (node (ref "D048") (pin "A") (pinfunction "A_A") (pintype "passive"))
      (node (ref "D052") (pin "C") (pinfunction "C_C") (pintype "passive"))
      (node (ref "D059") (pin "A") (pinfunction "A_A") (pintype "passive"))
      (node (ref "D104") (pin "C") (pinfunction "C_C") (pintype "passive"))
      (node (ref "D109") (pin "A") (pinfunction "A_A") (pintype "passive"))
      (node (ref "D118") (pin "A") (pinfunction "A_A") (pintype "passive"))
      (node (ref "D126") (pin "A") (pinfunction "A_A") (pintype "passive"))
      (node (ref "D133") (pin "A") (pinfunction "A_A") (pintype "passive"))
      (node (ref "D139") (pin "A") (pinfunction "A_A") (pintype "passive"))
      (node (ref "J405") (pin "3") (pinfunction "3_3") (pintype "passive"))
      (node (ref "R3") (pin "6") (pinfunction "2_6") (pintype "passive"))
    )
    (net (code "34") (name "/Q12") (class "Default")
      (node (ref "D010") (pin "A") (pinfunction "A_A") (pintype "passive"))
      (node (ref "D011") (pin "C") (pinfunction "C_C") (pintype "passive"))
      (node (ref "D024") (pin "A") (pinfunction "A_A") (pintype "passive"))
      (node (ref "D026") (pin "C") (pinfunction "C_C") (pintype "passive"))
      (node (ref "D037") (pin "A") (pinfunction "A_A") (pintype "passive"))
      (node (ref "D040") (pin "C") (pinfunction "C_C") (pintype "passive"))
      (node (ref "D049") (pin "A") (pinfunction "A_A") (pintype "passive"))
      (node (ref "D053") (pin "C") (pinfunction "C_C") (pintype "passive"))
      (node (ref "D100") (pin "A") (pinfunction "A_A") (pintype "passive"))
      (node (ref "D110") (pin "A") (pinfunction "A_A") (pintype "passive"))
      (node (ref "D119") (pin "A") (pinfunction "A_A") (pintype "passive"))
      (node (ref "D127") (pin "A") (pinfunction "A_A") (pintype "passive"))
      (node (ref "D134") (pin "A") (pinfunction "A_A") (pintype "passive"))
      (node (ref "D140") (pin "A") (pinfunction "A_A") (pintype "passive"))
      (node (ref "D145") (pin "A") (pinfunction "A_A") (pintype "passive"))
      (node (ref "J405") (pin "4") (pinfunction "4_4") (pintype "passive"))
      (node (ref "R3") (pin "5") (pinfunction "2_5") (pintype "passive"))
    )
    (net (code "35") (name "/Q13") (class "Default")
      (node (ref "D011") (pin "A") (pinfunction "A_A") (pintype "passive"))
      (node (ref "D012") (pin "C") (pinfunction "C_C") (pintype "passive"))
      (node (ref "D025") (pin "A") (pinfunction "A_A") (pintype "passive"))
      (node (ref "D027") (pin "C") (pinfunction "C_C") (pintype "passive"))
      (node (ref "D038") (pin "A") (pinfunction "A_A") (pintype "passive"))
      (node (ref "D041") (pin "C") (pinfunction "C_C") (pintype "passive"))
      (node (ref "D050") (pin "A") (pinfunction "A_A") (pintype "passive"))
      (node (ref "D101") (pin "A") (pinfunction "A_A") (pintype "passive"))
      (node (ref "D111") (pin "A") (pinfunction "A_A") (pintype "passive"))
      (node (ref "D120") (pin "A") (pinfunction "A_A") (pintype "passive"))
      (node (ref "D128") (pin "A") (pinfunction "A_A") (pintype "passive"))
      (node (ref "D135") (pin "A") (pinfunction "A_A") (pintype "passive"))
      (node (ref "D141") (pin "A") (pinfunction "A_A") (pintype "passive"))
      (node (ref "D146") (pin "A") (pinfunction "A_A") (pintype "passive"))
      (node (ref "D150") (pin "A") (pinfunction "A_A") (pintype "passive"))
      (node (ref "J405") (pin "5") (pinfunction "5_5") (pintype "passive"))
      (node (ref "R4") (pin "8") (pinfunction "2_8") (pintype "passive"))
    )
    (net (code "36") (name "/Q14") (class "Default")
      (node (ref "D012") (pin "A") (pinfunction "A_A") (pintype "passive"))
      (node (ref "D013") (pin "C") (pinfunction "C_C") (pintype "passive"))
      (node (ref "D026") (pin "A") (pinfunction "A_A") (pintype "passive"))
      (node (ref "D028") (pin "C") (pinfunction "C_C") (pintype "passive"))
      (node (ref "D039") (pin "A") (pinfunction "A_A") (pintype "passive"))
      (node (ref "D051") (pin "A") (pinfunction "A_A") (pintype "passive"))
      (node (ref "D102") (pin "A") (pinfunction "A_A") (pintype "passive"))
      (node (ref "D112") (pin "A") (pinfunction "A_A") (pintype "passive"))
      (node (ref "D121") (pin "A") (pinfunction "A_A") (pintype "passive"))
      (node (ref "D129") (pin "A") (pinfunction "A_A") (pintype "passive"))
      (node (ref "D136") (pin "A") (pinfunction "A_A") (pintype "passive"))
      (node (ref "D142") (pin "A") (pinfunction "A_A") (pintype "passive"))
      (node (ref "D147") (pin "A") (pinfunction "A_A") (pintype "passive"))
      (node (ref "D151") (pin "A") (pinfunction "A_A") (pintype "passive"))
      (node (ref "D154") (pin "A") (pinfunction "A_A") (pintype "passive"))
      (node (ref "J405") (pin "6") (pinfunction "6_6") (pintype "passive"))
      (node (ref "R4") (pin "7") (pinfunction "2_7") (pintype "passive"))
    )
    (net (code "37") (name "/Q15") (class "Default")
      (node (ref "D013") (pin "A") (pinfunction "A_A") (pintype "passive"))
      (node (ref "D014") (pin "C") (pinfunction "C_C") (pintype "passive"))
      (node (ref "D027") (pin "A") (pinfunction "A_A") (pintype "passive"))
      (node (ref "D040") (pin "A") (pinfunction "A_A") (pintype "passive"))
      (node (ref "D052") (pin "A") (pinfunction "A_A") (pintype "passive"))
      (node (ref "D103") (pin "A") (pinfunction "A_A") (pintype "passive"))
      (node (ref "D113") (pin "A") (pinfunction "A_A") (pintype "passive"))
      (node (ref "D122") (pin "A") (pinfunction "A_A") (pintype "passive"))
      (node (ref "D130") (pin "A") (pinfunction "A_A") (pintype "passive"))
      (node (ref "D137") (pin "A") (pinfunction "A_A") (pintype "passive"))
      (node (ref "D143") (pin "A") (pinfunction "A_A") (pintype "passive"))
      (node (ref "D148") (pin "A") (pinfunction "A_A") (pintype "passive"))
      (node (ref "D152") (pin "A") (pinfunction "A_A") (pintype "passive"))
      (node (ref "D155") (pin "A") (pinfunction "A_A") (pintype "passive"))
      (node (ref "D157") (pin "A") (pinfunction "A_A") (pintype "passive"))
      (node (ref "J405") (pin "7") (pinfunction "7_7") (pintype "passive"))
      (node (ref "R4") (pin "6") (pinfunction "2_6") (pintype "passive"))
    )
    (net (code "38") (name "/Q16") (class "Default")
      (node (ref "D014") (pin "A") (pinfunction "A_A") (pintype "passive"))
      (node (ref "D028") (pin "A") (pinfunction "A_A") (pintype "passive"))
      (node (ref "D041") (pin "A") (pinfunction "A_A") (pintype "passive"))
      (node (ref "D053") (pin "A") (pinfunction "A_A") (pintype "passive"))
      (node (ref "D104") (pin "A") (pinfunction "A_A") (pintype "passive"))
      (node (ref "D114") (pin "A") (pinfunction "A_A") (pintype "passive"))
      (node (ref "D123") (pin "A") (pinfunction "A_A") (pintype "passive"))
      (node (ref "D131") (pin "A") (pinfunction "A_A") (pintype "passive"))
      (node (ref "D138") (pin "A") (pinfunction "A_A") (pintype "passive"))
      (node (ref "D144") (pin "A") (pinfunction "A_A") (pintype "passive"))
      (node (ref "D149") (pin "A") (pinfunction "A_A") (pintype "passive"))
      (node (ref "D153") (pin "A") (pinfunction "A_A") (pintype "passive"))
      (node (ref "D156") (pin "A") (pinfunction "A_A") (pintype "passive"))
      (node (ref "D158") (pin "A") (pinfunction "A_A") (pintype "passive"))
      (node (ref "D159") (pin "A") (pinfunction "A_A") (pintype "passive"))
      (node (ref "J405") (pin "8") (pinfunction "8_8") (pintype "passive"))
      (node (ref "R4") (pin "5") (pinfunction "2_5") (pintype "passive"))
    )
    (net (code "39") (name "/RESET") (class "Default")
      (node (ref "C502") (pin "1") (pinfunction "1_1") (pintype "passive"))
      (node (ref "J003") (pin "1") (pinfunction "1_1") (pintype "passive"))
      (node (ref "R606") (pin "5") (pinfunction "2_5") (pintype "passive"))
      (node (ref "S429") (pin "P$2") (pinfunction "2_P$2") (pintype "bidirectional"))
      (node (ref "U401") (pin "29") (pinfunction "PC6(/RESET)_29") (pintype "bidirectional"))
    )
    (net (code "40") (name "/USBD+") (class "Default")
      (node (ref "J001") (pin "1") (pinfunction "1_1") (pintype "passive"))
      (node (ref "J002") (pin "1") (pinfunction "1_1") (pintype "passive"))
      (node (ref "U501") (pin "15") (pinfunction "USBDP_15") (pintype "bidirectional"))
    )
    (net (code "41") (name "/USBD-") (class "Default")
      (node (ref "J001") (pin "2") (pinfunction "2_2") (pintype "passive"))
      (node (ref "J002") (pin "2") (pinfunction "2_2") (pintype "passive"))
      (node (ref "U501") (pin "16") (pinfunction "USBDM_16") (pintype "bidirectional"))
    )
    (net (code "42") (name "/USB_TX") (class "Default")
      (node (ref "U501") (pin "1") (pinfunction "TXD_1") (pintype "output"))
      (node (ref "U602") (pin "1") (pinfunction "I1_1") (pintype "bidirectional"))
    )
    (net (code "43") (name "/XTAL1") (class "Default")
      (node (ref "C407") (pin "2") (pinfunction "2_2") (pintype "passive"))
      (node (ref "U401") (pin "7") (pinfunction "PB6(XTAL1/TOSC1)_7") (pintype "bidirectional"))
      (node (ref "Y401") (pin "1") (pinfunction "1_1") (pintype "passive"))
    )
    (net (code "44") (name "/XTAL2") (class "Default")
      (node (ref "C408") (pin "2") (pinfunction "2_2") (pintype "passive"))
      (node (ref "U401") (pin "8") (pinfunction "PB7(XTAL2/TOSC2)_8") (pintype "bidirectional"))
      (node (ref "Y401") (pin "3") (pinfunction "2_3") (pintype "passive"))
    )
    (net (code "45") (name "GND") (class "Default")
      (node (ref "C010") (pin "2") (pinfunction "2_2") (pintype "passive"))
      (node (ref "C407") (pin "1") (pinfunction "1_1") (pintype "passive"))
      (node (ref "C408") (pin "1") (pinfunction "1_1") (pintype "passive"))
      (node (ref "C418") (pin "1") (pinfunction "1_1") (pintype "passive"))
      (node (ref "C420") (pin "2") (pinfunction "2_2") (pintype "passive"))
      (node (ref "J001") (pin "4") (pinfunction "4_4") (pintype "passive"))
      (node (ref "J002") (pin "4") (pinfunction "4_4") (pintype "passive"))
      (node (ref "J003") (pin "3") (pinfunction "3_3") (pintype "passive"))
      (node (ref "J004") (pin "4") (pinfunction "4_4") (pintype "passive"))
      (node (ref "S429") (pin "P$1") (pinfunction "1_P$1") (pintype "bidirectional"))
      (node (ref "U401") (pin "21") (pinfunction "GND_21") (pintype "bidirectional"))
      (node (ref "U401") (pin "3") (pinfunction "GND_3") (pintype "bidirectional"))
      (node (ref "U401") (pin "5") (pinfunction "AGND_5") (pintype "bidirectional"))
      (node (ref "U501") (pin "18") (pinfunction "GND18_18") (pintype "power_in"))
      (node (ref "U501") (pin "21") (pinfunction "GND21_21") (pintype "power_in"))
      (node (ref "U501") (pin "25") (pinfunction "AGND_25") (pintype "power_in"))
      (node (ref "U501") (pin "26") (pinfunction "TEST_26") (pintype "input"))
      (node (ref "U501") (pin "7") (pinfunction "GND7_7") (pintype "power_in"))
      (node (ref "U602") (pin "2") (pinfunction "GND_2") (pintype "bidirectional"))
      (node (ref "Y401") (pin "2") (pinfunction "GND_2") (pintype "passive"))
      (node (ref "Y401") (pin "4") (pinfunction "GND_4") (pintype "passive"))
    )
    (net (code "46") (name "Net-(D501-PadC)") (class "Default")
      (node (ref "D501") (pin "C") (pinfunction "C_C") (pintype "passive"))
      (node (ref "R501") (pin "2") (pinfunction "2_2") (pintype "passive"))
    )
    (net (code "47") (name "Net-(D502-PadC)") (class "Default")
      (node (ref "D502") (pin "C") (pinfunction "C_C") (pintype "passive"))
      (node (ref "R502") (pin "2") (pinfunction "2_2") (pintype "passive"))
    )
    (net (code "48") (name "Net-(U401-AREF)") (class "Default")
      (node (ref "C420") (pin "1") (pinfunction "1_1") (pintype "passive"))
      (node (ref "U401") (pin "20") (pinfunction "AREF_20") (pintype "bidirectional"))
    )
    (net (code "49") (name "Net-(U501-DTR)") (class "Default")
      (node (ref "C502") (pin "2") (pinfunction "2_2") (pintype "passive"))
      (node (ref "U501") (pin "2") (pinfunction "DTR_2") (pintype "output"))
    )
    (net (code "50") (name "Net-(U501-RXLED)") (class "Default")
      (node (ref "R502") (pin "1") (pinfunction "1_1") (pintype "passive"))
      (node (ref "U501") (pin "22") (pinfunction "RXLED_22") (pintype "input"))
    )
    (net (code "51") (name "Net-(U501-TXLED)") (class "Default")
      (node (ref "R501") (pin "1") (pinfunction "1_1") (pintype "passive"))
      (node (ref "U501") (pin "23") (pinfunction "TXLED_23") (pintype "input"))
    )
    (net (code "52") (name "VCC") (class "Default")
      (node (ref "C010") (pin "1") (pinfunction "1_1") (pintype "passive"))
      (node (ref "C418") (pin "2") (pinfunction "2_2") (pintype "passive"))
      (node (ref "D501") (pin "A") (pinfunction "A_A") (pintype "passive"))
      (node (ref "D502") (pin "A") (pinfunction "A_A") (pintype "passive"))
      (node (ref "J001") (pin "3") (pinfunction "3_3") (pintype "passive"))
      (node (ref "J002") (pin "3") (pinfunction "3_3") (pintype "passive"))
      (node (ref "J003") (pin "2") (pinfunction "2_2") (pintype "passive"))
      (node (ref "R606") (pin "1") (pinfunction "1_1") (pintype "passive"))
      (node (ref "R606") (pin "4") (pinfunction "1_4") (pintype "passive"))
      (node (ref "U401") (pin "18") (pinfunction "AVCC_18") (pintype "bidirectional"))
      (node (ref "U401") (pin "4") (pinfunction "VCC_4") (pintype "bidirectional"))
      (node (ref "U401") (pin "6") (pinfunction "VCC_6") (pintype "bidirectional"))
      (node (ref "U501") (pin "20") (pinfunction "VCC_20") (pintype "power_in"))
      (node (ref "U501") (pin "4") (pinfunction "VCCIO_4") (pintype "power_in"))
      (node (ref "U602") (pin "5") (pinfunction "VCC_5") (pintype "bidirectional"))
    )
    (net (code "53") (name "unconnected-(U401-ADC6-Pad19)") (class "Default")
      (node (ref "U401") (pin "19") (pinfunction "ADC6_19") (pintype "bidirectional"))
    )
    (net (code "54") (name "unconnected-(U401-ADC7-Pad22)") (class "Default")
      (node (ref "U401") (pin "22") (pinfunction "ADC7_22") (pintype "bidirectional"))
    )
    (net (code "55") (name "unconnected-(U501-CTS-Pad11)") (class "Default")
      (node (ref "U501") (pin "11") (pinfunction "CTS_11") (pintype "input"))
    )
    (net (code "56") (name "unconnected-(U501-DCD-Pad10)") (class "Default")
      (node (ref "U501") (pin "10") (pinfunction "DCD_10") (pintype "input"))
    )
    (net (code "57") (name "unconnected-(U501-DSR-Pad9)") (class "Default")
      (node (ref "U501") (pin "9") (pinfunction "DSR_9") (pintype "input"))
    )
    (net (code "58") (name "unconnected-(U501-OSCI-Pad27)") (class "Default")
      (node (ref "U501") (pin "27") (pinfunction "OSCI_27") (pintype "input"))
    )
    (net (code "59") (name "unconnected-(U501-OSCO-Pad28)") (class "Default")
      (node (ref "U501") (pin "28") (pinfunction "OSCO_28") (pintype "output"))
    )
    (net (code "60") (name "unconnected-(U501-PWREN-Pad14)") (class "Default")
      (node (ref "U501") (pin "14") (pinfunction "PWREN_14") (pintype "input"))
    )
    (net (code "61") (name "unconnected-(U501-RESET-Pad19)") (class "Default")
      (node (ref "U501") (pin "19") (pinfunction "RESET_19") (pintype "input"))
    )
    (net (code "62") (name "unconnected-(U501-RI-Pad6)") (class "Default")
      (node (ref "U501") (pin "6") (pinfunction "RI_6") (pintype "input"))
    )
    (net (code "63") (name "unconnected-(U501-RTS-Pad3)") (class "Default")
      (node (ref "U501") (pin "3") (pinfunction "RTS_3") (pintype "output"))
    )
    (net (code "64") (name "unconnected-(U501-SLEEP-Pad12)") (class "Default")
      (node (ref "U501") (pin "12") (pinfunction "SLEEP_12") (pintype "input"))
    )
    (net (code "65") (name "unconnected-(U501-TXDEN-Pad13)") (class "Default")
      (node (ref "U501") (pin "13") (pinfunction "TXDEN_13") (pintype "input"))
    )
  )
)
